# control_panel.net
KiCad netlist of a schematic drawn in EAGLE
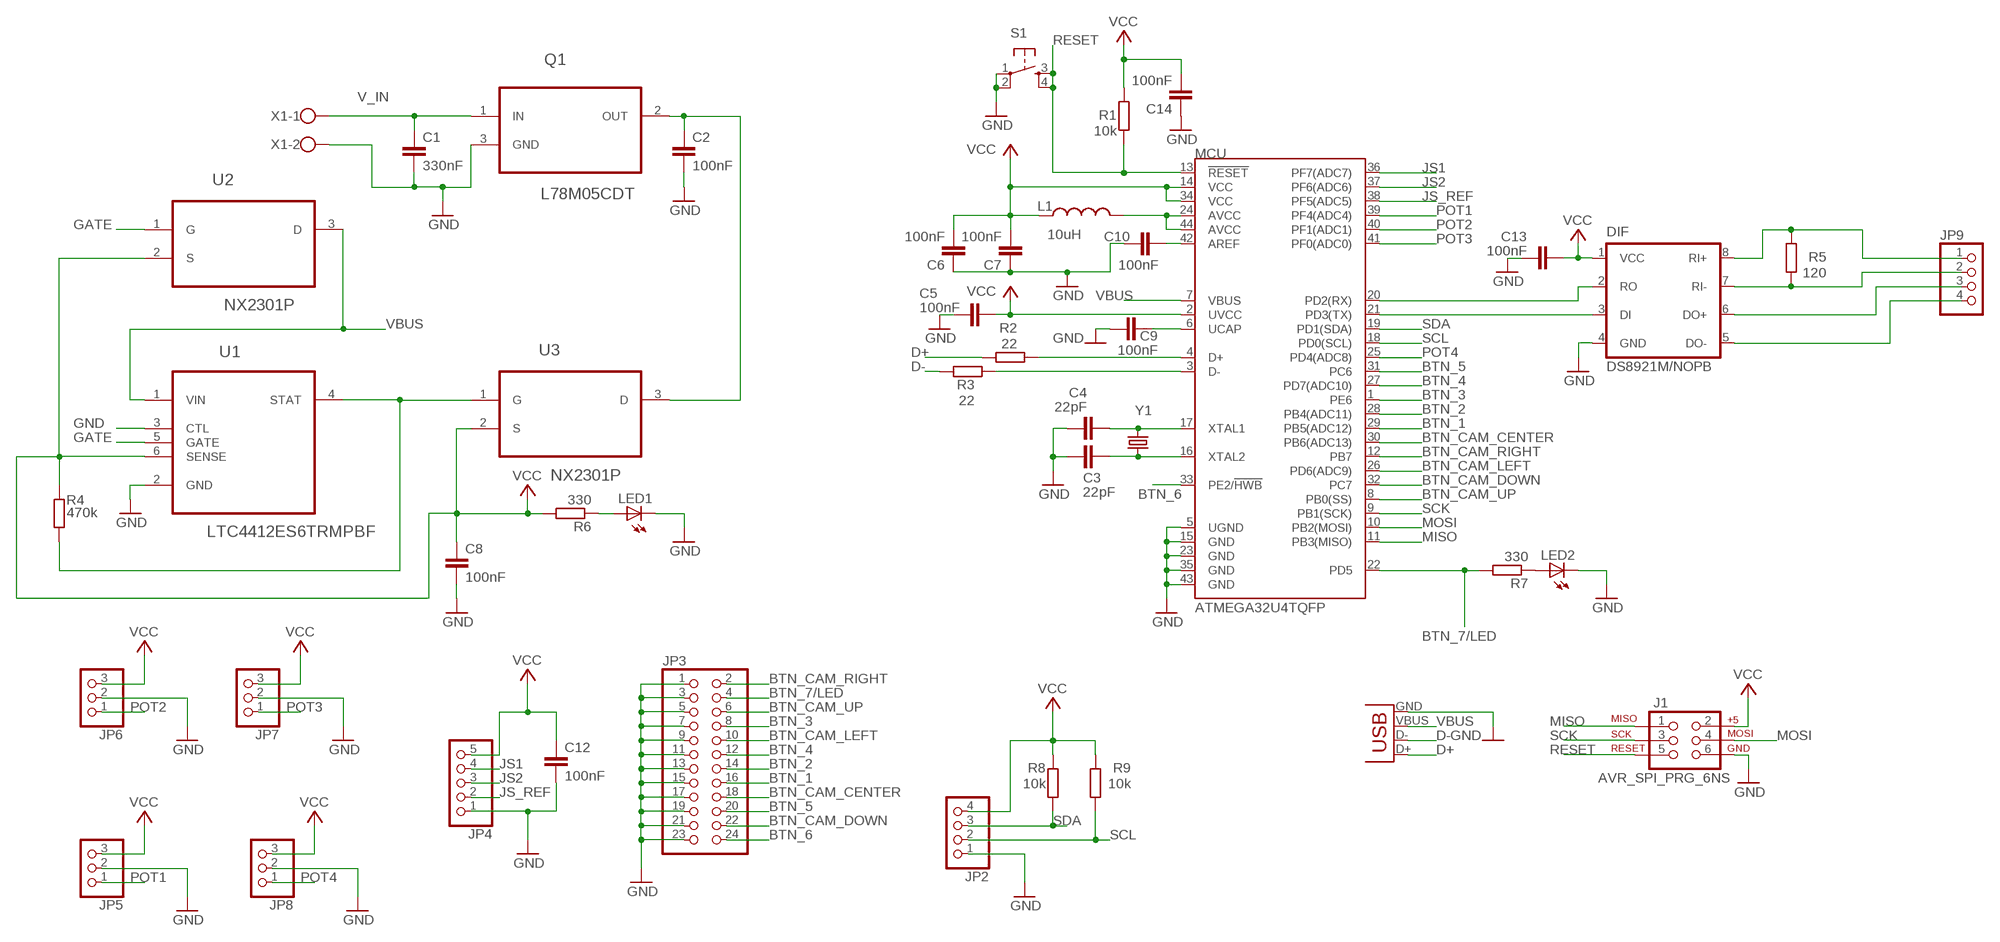
[diagram p0: schematic, sheet 1]

(export (version "E")
  (design (tool "Eeschema 10.0.6"))
  (components
    (comp (ref "C1")
      (value "330nF")
      (footprint "eagle-import:C0805")
      (libsource (lib "eagle-import") (part "C-EUC0805"))
    )
    (comp (ref "C2")
      (value "100nF")
      (footprint "eagle-import:C0805")
      (libsource (lib "eagle-import") (part "C-EUC0805"))
    )
    (comp (ref "C3")
      (value "22pF")
      (footprint "eagle-import:C0805")
      (libsource (lib "eagle-import") (part "C-EUC0805"))
    )
    (comp (ref "C4")
      (value "22pF")
      (footprint "eagle-import:C0805")
      (libsource (lib "eagle-import") (part "C-EUC0805"))
    )
    (comp (ref "C5")
      (value "100nF")
      (footprint "eagle-import:C0805")
      (libsource (lib "eagle-import") (part "C-EUC0805"))
    )
    (comp (ref "C6")
      (value "100nF")
      (footprint "eagle-import:C0805")
      (libsource (lib "eagle-import") (part "C-EUC0805"))
    )
    (comp (ref "C7")
      (value "100nF")
      (footprint "eagle-import:C0805")
      (libsource (lib "eagle-import") (part "C-EUC0805"))
    )
    (comp (ref "C8")
      (value "100nF")
      (footprint "eagle-import:C0805")
      (libsource (lib "eagle-import") (part "C-EUC0805"))
    )
    (comp (ref "C9")
      (value "100nF")
      (footprint "eagle-import:C0805")
      (libsource (lib "eagle-import") (part "C-EUC0805"))
    )
    (comp (ref "C10")
      (value "100nF")
      (footprint "eagle-import:C0805")
      (libsource (lib "eagle-import") (part "C-EUC0805"))
    )
    (comp (ref "C12")
      (value "100nF")
      (footprint "eagle-import:C0805")
      (libsource (lib "eagle-import") (part "C-EUC0805"))
    )
    (comp (ref "C13")
      (value "100nF")
      (footprint "eagle-import:C0805")
      (libsource (lib "eagle-import") (part "C-EUC0805"))
    )
    (comp (ref "C14")
      (value "100nF")
      (footprint "eagle-import:C0805")
      (libsource (lib "eagle-import") (part "C-EUC0805"))
    )
    (comp (ref "DIF")
      (value "DS8921M/NOPB")
      (footprint "eagle-import:SOIC8")
      (libsource (lib "eagle-import") (part "DS8921M/NOPB"))
    )
    (comp (ref "J1")
      (value "AVR_SPI_PRG_6NS")
      (footprint "eagle-import:2X3-NS")
      (libsource (lib "eagle-import") (part "AVR_SPI_PRG_6NS"))
    )
    (comp (ref "JP1")
      (value "USB-B")
      (footprint "eagle-import:USB-B-PTH")
      (libsource (lib "eagle-import") (part "USBPTH"))
    )
    (comp (ref "JP2")
      (value "PINHD-1X4")
      (footprint "eagle-import:1X04")
      (libsource (lib "eagle-import") (part "PINHD-1X4"))
    )
    (comp (ref "JP3")
      (value "PINHD-2X12")
      (footprint "eagle-import:2X12")
      (libsource (lib "eagle-import") (part "PINHD-2X12"))
    )
    (comp (ref "JP4")
      (value "PINHD-1X5")
      (footprint "eagle-import:1X05")
      (libsource (lib "eagle-import") (part "PINHD-1X5"))
    )
    (comp (ref "JP5")
      (value "PINHD-1X3")
      (footprint "eagle-import:1X03")
      (libsource (lib "eagle-import") (part "PINHD-1X3"))
    )
    (comp (ref "JP6")
      (value "PINHD-1X3")
      (footprint "eagle-import:1X03")
      (libsource (lib "eagle-import") (part "PINHD-1X3"))
    )
    (comp (ref "JP7")
      (value "PINHD-1X3")
      (footprint "eagle-import:1X03")
      (libsource (lib "eagle-import") (part "PINHD-1X3"))
    )
    (comp (ref "JP8")
      (value "PINHD-1X3")
      (footprint "eagle-import:1X03")
      (libsource (lib "eagle-import") (part "PINHD-1X3"))
    )
    (comp (ref "JP9")
      (value "PINHD-1X4")
      (footprint "eagle-import:1X04")
      (libsource (lib "eagle-import") (part "PINHD-1X4"))
    )
    (comp (ref "L1")
      (value "10uH")
      (footprint "eagle-import:0805")
      (libsource (lib "eagle-import") (part "INDUCTOR0805"))
    )
    (comp (ref "LED1")
      (value "LED-FKIT-1206")
      (footprint "eagle-import:FKIT-LED-1206")
      (libsource (lib "eagle-import") (part "LED-FKIT-1206"))
    )
    (comp (ref "LED2")
      (value "LED-FKIT-1206")
      (footprint "eagle-import:FKIT-LED-1206")
      (libsource (lib "eagle-import") (part "LED-FKIT-1206"))
    )
    (comp (ref "MCU")
      (value "ATMEGA32U4TQFP")
      (footprint "eagle-import:SPARKFUN-DIGITALIC_TQFP44")
      (libsource (lib "eagle-import") (part "ATMEGA32U4TQFP"))
    )
    (comp (ref "Q1")
      (value "L78M05CDT")
      (footprint "eagle-import:TO225P972X240-3N")
      (libsource (lib "eagle-import") (part "L78M05CDT"))
    )
    (comp (ref "R1")
      (value "10k")
      (footprint "eagle-import:R0805")
      (libsource (lib "eagle-import") (part "R-EU_R0805"))
    )
    (comp (ref "R2")
      (value "22")
      (footprint "eagle-import:R0805")
      (libsource (lib "eagle-import") (part "R-EU_R0805"))
    )
    (comp (ref "R3")
      (value "22")
      (footprint "eagle-import:R0805")
      (libsource (lib "eagle-import") (part "R-EU_R0805"))
    )
    (comp (ref "R4")
      (value "470k")
      (footprint "eagle-import:R0805")
      (libsource (lib "eagle-import") (part "R-EU_R0805"))
    )
    (comp (ref "R5")
      (value "120")
      (footprint "eagle-import:R0805")
      (libsource (lib "eagle-import") (part "R-EU_R0805"))
    )
    (comp (ref "R6")
      (value "330")
      (footprint "eagle-import:R0805")
      (libsource (lib "eagle-import") (part "R-EU_R0805"))
    )
    (comp (ref "R7")
      (value "330")
      (footprint "eagle-import:R0805")
      (libsource (lib "eagle-import") (part "R-EU_R0805"))
    )
    (comp (ref "R8")
      (value "10k")
      (footprint "eagle-import:R0805")
      (libsource (lib "eagle-import") (part "R-EU_R0805"))
    )
    (comp (ref "R9")
      (value "10k")
      (footprint "eagle-import:R0805")
      (libsource (lib "eagle-import") (part "R-EU_R0805"))
    )
    (comp (ref "S1")
      (value "TAC_SWITCHSMD")
      (footprint "eagle-import:TACTILE_SWITCH_SMD")
      (libsource (lib "eagle-import") (part "TAC_SWITCHSMD"))
    )
    (comp (ref "U1")
      (value "LTC4412ES6TRMPBF")
      (footprint "eagle-import:SOT95P280X100-6N")
      (fields (field (name "MPN") "LTC4412ES6#TRMPBF"))
      (libsource (lib "eagle-import") (part "LTC4412ES6TRMPBF"))
    )
    (comp (ref "U2")
      (value "NX2301P")
      (footprint "eagle-import:SOT95P230X110-3N")
      (libsource (lib "eagle-import") (part "NX2301P"))
    )
    (comp (ref "U3")
      (value "NX2301P")
      (footprint "eagle-import:SOT95P230X110-3N")
      (libsource (lib "eagle-import") (part "NX2301P"))
    )
    (comp (ref "X1")
      (value "W237-102")
      (footprint "eagle-import:W237-102")
      (fields (field (name "MPN") "237-102"))
      (libsource (lib "eagle-import") (part "W237-102"))
    )
    (comp (ref "Y1")
      (value "CRYSTALSMD")
      (footprint "eagle-import:HC49UP")
      (libsource (lib "eagle-import") (part "CRYSTALSMD"))
    )
  )
  (nets
    (net (code "1") (name "/BTN_1") (class "Default")
      (node (ref "JP3") (pin "16") (pinfunction "16_16") (pintype "passive"))
      (node (ref "MCU") (pin "29") (pinfunction "PB5(ADC12)_29") (pintype "bidirectional"))
    )
    (net (code "2") (name "/BTN_2") (class "Default")
      (node (ref "JP3") (pin "14") (pinfunction "14_14") (pintype "passive"))
      (node (ref "MCU") (pin "28") (pinfunction "PB4(ADC11)_28") (pintype "bidirectional"))
    )
    (net (code "3") (name "/BTN_3") (class "Default")
      (node (ref "JP3") (pin "8") (pinfunction "8_8") (pintype "passive"))
      (node (ref "MCU") (pin "1") (pinfunction "PE6_1") (pintype "bidirectional"))
    )
    (net (code "4") (name "/BTN_4") (class "Default")
      (node (ref "JP3") (pin "12") (pinfunction "12_12") (pintype "passive"))
      (node (ref "MCU") (pin "27") (pinfunction "PD7(ADC10)_27") (pintype "bidirectional"))
    )
    (net (code "5") (name "/BTN_5") (class "Default")
      (node (ref "JP3") (pin "20") (pinfunction "20_20") (pintype "passive"))
      (node (ref "MCU") (pin "31") (pinfunction "PC6_31") (pintype "bidirectional"))
    )
    (net (code "6") (name "/BTN_6") (class "Default")
      (node (ref "JP3") (pin "24") (pinfunction "24_24") (pintype "passive"))
      (node (ref "MCU") (pin "33") (pinfunction "PE2/~{HWB}_33") (pintype "bidirectional"))
    )
    (net (code "7") (name "/BTN_7{slash}LED") (class "Default")
      (node (ref "JP3") (pin "4") (pinfunction "4_4") (pintype "passive"))
      (node (ref "MCU") (pin "22") (pinfunction "PD5_22") (pintype "bidirectional"))
      (node (ref "R7") (pin "2") (pinfunction "2_2") (pintype "passive"))
    )
    (net (code "8") (name "/BTN_CAM_CENTER") (class "Default")
      (node (ref "JP3") (pin "18") (pinfunction "18_18") (pintype "passive"))
      (node (ref "MCU") (pin "30") (pinfunction "PB6(ADC13)_30") (pintype "bidirectional"))
    )
    (net (code "9") (name "/BTN_CAM_DOWN") (class "Default")
      (node (ref "JP3") (pin "22") (pinfunction "22_22") (pintype "passive"))
      (node (ref "MCU") (pin "32") (pinfunction "PC7_32") (pintype "bidirectional"))
    )
    (net (code "10") (name "/BTN_CAM_LEFT") (class "Default")
      (node (ref "JP3") (pin "10") (pinfunction "10_10") (pintype "passive"))
      (node (ref "MCU") (pin "26") (pinfunction "PD6(ADC9)_26") (pintype "bidirectional"))
    )
    (net (code "11") (name "/BTN_CAM_RIGHT") (class "Default")
      (node (ref "JP3") (pin "2") (pinfunction "2_2") (pintype "passive"))
      (node (ref "MCU") (pin "12") (pinfunction "PB7_12") (pintype "bidirectional"))
    )
    (net (code "12") (name "/BTN_CAM_UP") (class "Default")
      (node (ref "JP3") (pin "6") (pinfunction "6_6") (pintype "passive"))
      (node (ref "MCU") (pin "8") (pinfunction "PB0(SS)_8") (pintype "bidirectional"))
    )
    (net (code "13") (name "/D+") (class "Default")
      (node (ref "JP1") (pin "D+") (pinfunction "D+_D+") (pintype "bidirectional"))
      (node (ref "R2") (pin "2") (pinfunction "2_2") (pintype "passive"))
    )
    (net (code "14") (name "/D-") (class "Default")
      (node (ref "JP1") (pin "D-") (pinfunction "D-_D-") (pintype "bidirectional"))
      (node (ref "R3") (pin "2") (pinfunction "2_2") (pintype "passive"))
    )
    (net (code "15") (name "/GATE") (class "Default")
      (node (ref "U1") (pin "5") (pinfunction "GATE_5") (pintype "input"))
      (node (ref "U2") (pin "1") (pinfunction "G_1") (pintype "passive"))
    )
    (net (code "16") (name "/JS1") (class "Default")
      (node (ref "JP4") (pin "4") (pinfunction "4_4") (pintype "passive"))
      (node (ref "MCU") (pin "36") (pinfunction "PF7(ADC7)_36") (pintype "bidirectional"))
    )
    (net (code "17") (name "/JS2") (class "Default")
      (node (ref "JP4") (pin "3") (pinfunction "3_3") (pintype "passive"))
      (node (ref "MCU") (pin "37") (pinfunction "PF6(ADC6)_37") (pintype "bidirectional"))
    )
    (net (code "18") (name "/JS_REF") (class "Default")
      (node (ref "JP4") (pin "2") (pinfunction "2_2") (pintype "passive"))
      (node (ref "MCU") (pin "38") (pinfunction "PF5(ADC5)_38") (pintype "bidirectional"))
    )
    (net (code "19") (name "/MISO") (class "Default")
      (node (ref "J1") (pin "1") (pinfunction "1_1") (pintype "passive"))
      (node (ref "MCU") (pin "11") (pinfunction "PB3(MISO)_11") (pintype "bidirectional"))
    )
    (net (code "20") (name "/MOSI") (class "Default")
      (node (ref "J1") (pin "4") (pinfunction "4_4") (pintype "passive"))
      (node (ref "MCU") (pin "10") (pinfunction "PB2(MOSI)_10") (pintype "bidirectional"))
    )
    (net (code "21") (name "/POT1") (class "Default")
      (node (ref "JP5") (pin "1") (pinfunction "1_1") (pintype "passive"))
      (node (ref "MCU") (pin "39") (pinfunction "PF4(ADC4)_39") (pintype "bidirectional"))
    )
    (net (code "22") (name "/POT2") (class "Default")
      (node (ref "JP6") (pin "1") (pinfunction "1_1") (pintype "passive"))
      (node (ref "MCU") (pin "40") (pinfunction "PF1(ADC1)_40") (pintype "bidirectional"))
    )
    (net (code "23") (name "/POT3") (class "Default")
      (node (ref "JP7") (pin "1") (pinfunction "1_1") (pintype "passive"))
      (node (ref "MCU") (pin "41") (pinfunction "PF0(ADC0)_41") (pintype "bidirectional"))
    )
    (net (code "24") (name "/POT4") (class "Default")
      (node (ref "JP8") (pin "1") (pinfunction "1_1") (pintype "passive"))
      (node (ref "MCU") (pin "25") (pinfunction "PD4(ADC8)_25") (pintype "bidirectional"))
    )
    (net (code "25") (name "/RESET") (class "Default")
      (node (ref "J1") (pin "5") (pinfunction "5_5") (pintype "passive"))
      (node (ref "MCU") (pin "13") (pinfunction "~{RESET}_13") (pintype "bidirectional"))
      (node (ref "R1") (pin "1") (pinfunction "1_1") (pintype "passive"))
      (node (ref "S1") (pin "3") (pinfunction "3_3") (pintype "passive"))
      (node (ref "S1") (pin "4") (pinfunction "4_4") (pintype "passive"))
    )
    (net (code "26") (name "/SCK") (class "Default")
      (node (ref "J1") (pin "3") (pinfunction "3_3") (pintype "passive"))
      (node (ref "MCU") (pin "9") (pinfunction "PB1(SCK)_9") (pintype "bidirectional"))
    )
    (net (code "27") (name "/SCL") (class "Default")
      (node (ref "JP2") (pin "2") (pinfunction "2_2") (pintype "passive"))
      (node (ref "MCU") (pin "18") (pinfunction "PD0(SCL)_18") (pintype "bidirectional"))
      (node (ref "R9") (pin "1") (pinfunction "1_1") (pintype "passive"))
    )
    (net (code "28") (name "/SDA") (class "Default")
      (node (ref "JP2") (pin "3") (pinfunction "3_3") (pintype "passive"))
      (node (ref "MCU") (pin "19") (pinfunction "PD1(SDA)_19") (pintype "bidirectional"))
      (node (ref "R8") (pin "1") (pinfunction "1_1") (pintype "passive"))
    )
    (net (code "29") (name "/VBUS") (class "Default")
      (node (ref "JP1") (pin "VBUS") (pinfunction "VBUS_VBUS") (pintype "bidirectional"))
      (node (ref "MCU") (pin "7") (pinfunction "VBUS_7") (pintype "bidirectional"))
      (node (ref "U1") (pin "1") (pinfunction "VIN_1") (pintype "power_in"))
      (node (ref "U2") (pin "3") (pinfunction "D_3") (pintype "passive"))
    )
    (net (code "30") (name "/V_IN") (class "Default")
      (node (ref "C1") (pin "1") (pinfunction "1_1") (pintype "passive"))
      (node (ref "Q1") (pin "1") (pinfunction "IN_1") (pintype "input"))
      (node (ref "X1") (pin "1") (pinfunction "KL_1") (pintype "passive"))
    )
    (net (code "31") (name "GND") (class "Default")
      (node (ref "C1") (pin "2") (pinfunction "2_2") (pintype "passive"))
      (node (ref "C10") (pin "2") (pinfunction "2_2") (pintype "passive"))
      (node (ref "C12") (pin "2") (pinfunction "2_2") (pintype "passive"))
      (node (ref "C13") (pin "1") (pinfunction "1_1") (pintype "passive"))
      (node (ref "C14") (pin "1") (pinfunction "1_1") (pintype "passive"))
      (node (ref "C2") (pin "2") (pinfunction "2_2") (pintype "passive"))
      (node (ref "C3") (pin "1") (pinfunction "1_1") (pintype "passive"))
      (node (ref "C4") (pin "1") (pinfunction "1_1") (pintype "passive"))
      (node (ref "C5") (pin "2") (pinfunction "2_2") (pintype "passive"))
      (node (ref "C6") (pin "1") (pinfunction "1_1") (pintype "passive"))
      (node (ref "C7") (pin "1") (pinfunction "1_1") (pintype "passive"))
      (node (ref "C8") (pin "2") (pinfunction "2_2") (pintype "passive"))
      (node (ref "C9") (pin "1") (pinfunction "1_1") (pintype "passive"))
      (node (ref "DIF") (pin "4") (pinfunction "GND_4") (pintype "power_in"))
      (node (ref "J1") (pin "6") (pinfunction "6_6") (pintype "passive"))
      (node (ref "JP1") (pin "GND") (pinfunction "GND_GND") (pintype "bidirectional"))
      (node (ref "JP2") (pin "1") (pinfunction "1_1") (pintype "passive"))
      (node (ref "JP3") (pin "1") (pinfunction "1_1") (pintype "passive"))
      (node (ref "JP3") (pin "11") (pinfunction "11_11") (pintype "passive"))
      (node (ref "JP3") (pin "13") (pinfunction "13_13") (pintype "passive"))
      (node (ref "JP3") (pin "15") (pinfunction "15_15") (pintype "passive"))
      (node (ref "JP3") (pin "17") (pinfunction "17_17") (pintype "passive"))
      (node (ref "JP3") (pin "19") (pinfunction "19_19") (pintype "passive"))
      (node (ref "JP3") (pin "21") (pinfunction "21_21") (pintype "passive"))
      (node (ref "JP3") (pin "23") (pinfunction "23_23") (pintype "passive"))
      (node (ref "JP3") (pin "3") (pinfunction "3_3") (pintype "passive"))
      (node (ref "JP3") (pin "5") (pinfunction "5_5") (pintype "passive"))
      (node (ref "JP3") (pin "7") (pinfunction "7_7") (pintype "passive"))
      (node (ref "JP3") (pin "9") (pinfunction "9_9") (pintype "passive"))
      (node (ref "JP4") (pin "1") (pinfunction "1_1") (pintype "passive"))
      (node (ref "JP5") (pin "2") (pinfunction "2_2") (pintype "passive"))
      (node (ref "JP6") (pin "2") (pinfunction "2_2") (pintype "passive"))
      (node (ref "JP7") (pin "2") (pinfunction "2_2") (pintype "passive"))
      (node (ref "JP8") (pin "2") (pinfunction "2_2") (pintype "passive"))
      (node (ref "LED1") (pin "C") (pinfunction "C_C") (pintype "passive"))
      (node (ref "LED2") (pin "C") (pinfunction "C_C") (pintype "passive"))
      (node (ref "MCU") (pin "15") (pinfunction "GND_15") (pintype "bidirectional"))
      (node (ref "MCU") (pin "23") (pinfunction "GND_23") (pintype "bidirectional"))
      (node (ref "MCU") (pin "35") (pinfunction "GND_35") (pintype "bidirectional"))
      (node (ref "MCU") (pin "43") (pinfunction "GND_43") (pintype "bidirectional"))
      (node (ref "MCU") (pin "5") (pinfunction "UGND_5") (pintype "bidirectional"))
      (node (ref "Q1") (pin "3") (pinfunction "GND_3") (pintype "passive"))
      (node (ref "S1") (pin "1") (pinfunction "1_1") (pintype "passive"))
      (node (ref "S1") (pin "2") (pinfunction "2_2") (pintype "passive"))
      (node (ref "U1") (pin "2") (pinfunction "GND_2") (pintype "passive"))
      (node (ref "U1") (pin "3") (pinfunction "CTL_3") (pintype "input"))
      (node (ref "X1") (pin "2") (pinfunction "KL_2") (pintype "passive"))
    )
    (net (code "32") (name "Net-(DIF-DI)") (class "Default")
      (node (ref "DIF") (pin "3") (pinfunction "DI_3") (pintype "input"))
      (node (ref "MCU") (pin "21") (pinfunction "PD3(TX)_21") (pintype "bidirectional"))
    )
    (net (code "33") (name "Net-(DIF-DO+)") (class "Default")
      (node (ref "DIF") (pin "6") (pinfunction "DO+_6") (pintype "output"))
      (node (ref "JP9") (pin "3") (pinfunction "3_3") (pintype "passive"))
    )
    (net (code "34") (name "Net-(DIF-DO-)") (class "Default")
      (node (ref "DIF") (pin "5") (pinfunction "DO-_5") (pintype "output"))
      (node (ref "JP9") (pin "4") (pinfunction "4_4") (pintype "passive"))
    )
    (net (code "35") (name "Net-(DIF-RI+)") (class "Default")
      (node (ref "DIF") (pin "8") (pinfunction "RI+_8") (pintype "input"))
      (node (ref "JP9") (pin "1") (pinfunction "1_1") (pintype "passive"))
      (node (ref "R5") (pin "2") (pinfunction "2_2") (pintype "passive"))
    )
    (net (code "36") (name "Net-(DIF-RI-)") (class "Default")
      (node (ref "DIF") (pin "7") (pinfunction "RI-_7") (pintype "input"))
      (node (ref "JP9") (pin "2") (pinfunction "2_2") (pintype "passive"))
      (node (ref "R5") (pin "1") (pinfunction "1_1") (pintype "passive"))
    )
    (net (code "37") (name "Net-(DIF-RO)") (class "Default")
      (node (ref "DIF") (pin "2") (pinfunction "RO_2") (pintype "output"))
      (node (ref "MCU") (pin "20") (pinfunction "PD2(RX)_20") (pintype "bidirectional"))
    )
    (net (code "38") (name "Net-(L1-Pad2)") (class "Default")
      (node (ref "L1") (pin "2") (pinfunction "2_2") (pintype "passive"))
      (node (ref "MCU") (pin "24") (pinfunction "AVCC_24") (pintype "bidirectional"))
      (node (ref "MCU") (pin "44") (pinfunction "AVCC_44") (pintype "bidirectional"))
    )
    (net (code "39") (name "Net-(LED1-PadA)") (class "Default")
      (node (ref "LED1") (pin "A") (pinfunction "A_A") (pintype "passive"))
      (node (ref "R6") (pin "1") (pinfunction "1_1") (pintype "passive"))
    )
    (net (code "40") (name "Net-(LED2-PadA)") (class "Default")
      (node (ref "LED2") (pin "A") (pinfunction "A_A") (pintype "passive"))
      (node (ref "R7") (pin "1") (pinfunction "1_1") (pintype "passive"))
    )
    (net (code "41") (name "Net-(MCU-AREF)") (class "Default")
      (node (ref "C10") (pin "1") (pinfunction "1_1") (pintype "passive"))
      (node (ref "MCU") (pin "42") (pinfunction "AREF_42") (pintype "bidirectional"))
    )
    (net (code "42") (name "Net-(MCU-D+)") (class "Default")
      (node (ref "MCU") (pin "4") (pinfunction "D+_4") (pintype "bidirectional"))
      (node (ref "R2") (pin "1") (pinfunction "1_1") (pintype "passive"))
    )
    (net (code "43") (name "Net-(MCU-D-)") (class "Default")
      (node (ref "MCU") (pin "3") (pinfunction "D-_3") (pintype "bidirectional"))
      (node (ref "R3") (pin "1") (pinfunction "1_1") (pintype "passive"))
    )
    (net (code "44") (name "Net-(MCU-UCAP)") (class "Default")
      (node (ref "C9") (pin "2") (pinfunction "2_2") (pintype "passive"))
      (node (ref "MCU") (pin "6") (pinfunction "UCAP_6") (pintype "bidirectional"))
    )
    (net (code "45") (name "Net-(MCU-XTAL1)") (class "Default")
      (node (ref "C4") (pin "2") (pinfunction "2_2") (pintype "passive"))
      (node (ref "MCU") (pin "17") (pinfunction "XTAL1_17") (pintype "bidirectional"))
      (node (ref "Y1") (pin "2") (pinfunction "2_2") (pintype "passive"))
    )
    (net (code "46") (name "Net-(MCU-XTAL2)") (class "Default")
      (node (ref "C3") (pin "2") (pinfunction "2_2") (pintype "passive"))
      (node (ref "MCU") (pin "16") (pinfunction "XTAL2_16") (pintype "bidirectional"))
      (node (ref "Y1") (pin "1") (pinfunction "1_1") (pintype "passive"))
    )
    (net (code "47") (name "Net-(Q1-OUT)") (class "Default")
      (node (ref "C2") (pin "1") (pinfunction "1_1") (pintype "passive"))
      (node (ref "Q1") (pin "2") (pinfunction "OUT_2") (pintype "output"))
      (node (ref "U3") (pin "3") (pinfunction "D_3") (pintype "passive"))
    )
    (net (code "48") (name "Net-(U1-STAT)") (class "Default")
      (node (ref "R4") (pin "2") (pinfunction "2_2") (pintype "passive"))
      (node (ref "U1") (pin "4") (pinfunction "STAT_4") (pintype "output"))
      (node (ref "U3") (pin "1") (pinfunction "G_1") (pintype "passive"))
    )
    (net (code "49") (name "VCC") (class "Default")
      (node (ref "C12") (pin "1") (pinfunction "1_1") (pintype "passive"))
      (node (ref "C13") (pin "2") (pinfunction "2_2") (pintype "passive"))
      (node (ref "C14") (pin "2") (pinfunction "2_2") (pintype "passive"))
      (node (ref "C5") (pin "1") (pinfunction "1_1") (pintype "passive"))
      (node (ref "C6") (pin "2") (pinfunction "2_2") (pintype "passive"))
      (node (ref "C7") (pin "2") (pinfunction "2_2") (pintype "passive"))
      (node (ref "C8") (pin "1") (pinfunction "1_1") (pintype "passive"))
      (node (ref "DIF") (pin "1") (pinfunction "VCC_1") (pintype "power_in"))
      (node (ref "J1") (pin "2") (pinfunction "2_2") (pintype "passive"))
      (node (ref "JP2") (pin "4") (pinfunction "4_4") (pintype "passive"))
      (node (ref "JP4") (pin "5") (pinfunction "5_5") (pintype "passive"))
      (node (ref "JP5") (pin "3") (pinfunction "3_3") (pintype "passive"))
      (node (ref "JP6") (pin "3") (pinfunction "3_3") (pintype "passive"))
      (node (ref "JP7") (pin "3") (pinfunction "3_3") (pintype "passive"))
      (node (ref "JP8") (pin "3") (pinfunction "3_3") (pintype "passive"))
      (node (ref "L1") (pin "1") (pinfunction "1_1") (pintype "passive"))
      (node (ref "MCU") (pin "14") (pinfunction "VCC_14") (pintype "bidirectional"))
      (node (ref "MCU") (pin "2") (pinfunction "UVCC_2") (pintype "bidirectional"))
      (node (ref "MCU") (pin "34") (pinfunction "VCC_34") (pintype "bidirectional"))
      (node (ref "R1") (pin "2") (pinfunction "2_2") (pintype "passive"))
      (node (ref "R4") (pin "1") (pinfunction "1_1") (pintype "passive"))
      (node (ref "R6") (pin "2") (pinfunction "2_2") (pintype "passive"))
      (node (ref "R8") (pin "2") (pinfunction "2_2") (pintype "passive"))
      (node (ref "R9") (pin "2") (pinfunction "2_2") (pintype "passive"))
      (node (ref "U1") (pin "6") (pinfunction "SENSE_6") (pintype "input"))
      (node (ref "U2") (pin "2") (pinfunction "S_2") (pintype "passive"))
      (node (ref "U3") (pin "2") (pinfunction "S_2") (pintype "passive"))
    )
  )
)
